# aiotdaan_r2.net
KiCad netlist of a schematic drawn in EAGLE
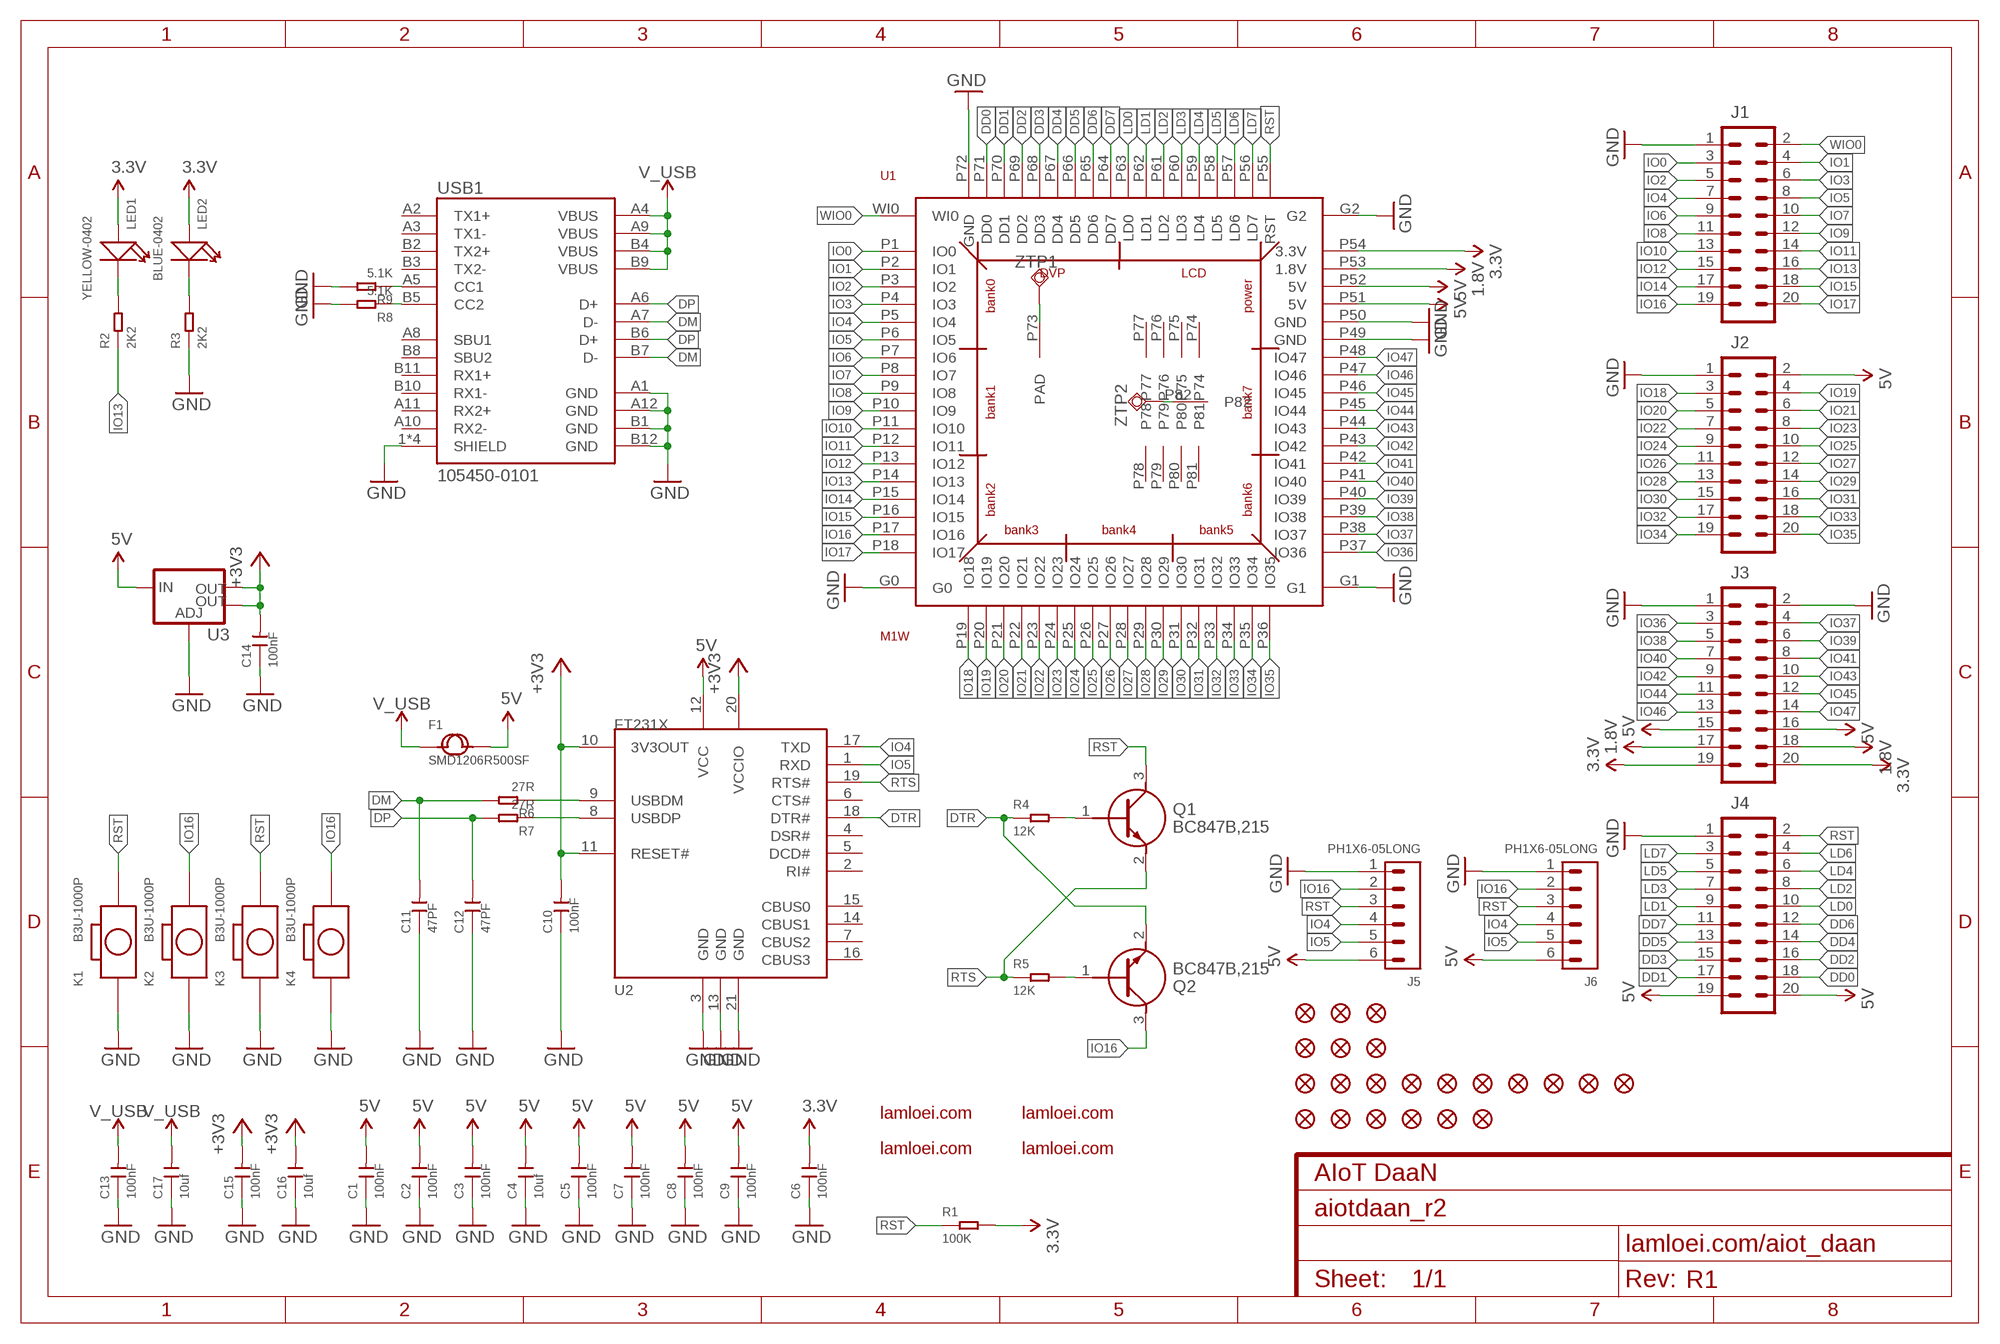
[diagram p0: schematic, sheet 1]

(export (version "E")
  (design (tool "Eeschema 10.0.6"))
  (components
    (comp (ref "C1")
      (value "100nF")
      (footprint "eagle-import:C0402")
      (fields (field (name "MPN") "CC0402JRNPO9BN470"))
      (libsource (lib "eagle-import") (part "CERAMIC-47PF-50V-5%-NP0(0402)"))
    )
    (comp (ref "C2")
      (value "100nF")
      (footprint "eagle-import:C0402")
      (fields (field (name "MPN") "CC0402JRNPO9BN470"))
      (libsource (lib "eagle-import") (part "CERAMIC-47PF-50V-5%-NP0(0402)"))
    )
    (comp (ref "C3")
      (value "100nF")
      (footprint "eagle-import:C0402")
      (fields (field (name "MPN") "CC0402JRNPO9BN470"))
      (libsource (lib "eagle-import") (part "CERAMIC-47PF-50V-5%-NP0(0402)"))
    )
    (comp (ref "C4")
      (value "10uf")
      (footprint "eagle-import:C0805")
      (fields (field (name "MPN") "CC0805MKX5R5BB226"))
      (libsource (lib "eagle-import") (part "CERAMIC-22UF-6.3V-20%-X5R(0805)"))
    )
    (comp (ref "C5")
      (value "100nF")
      (footprint "eagle-import:C0402")
      (fields (field (name "MPN") "CC0402JRNPO9BN470"))
      (libsource (lib "eagle-import") (part "CERAMIC-47PF-50V-5%-NP0(0402)"))
    )
    (comp (ref "C6")
      (value "100nF")
      (footprint "eagle-import:C0402")
      (fields (field (name "MPN") "CC0402JRNPO9BN470"))
      (libsource (lib "eagle-import") (part "CERAMIC-47PF-50V-5%-NP0(0402)"))
    )
    (comp (ref "C7")
      (value "100nF")
      (footprint "eagle-import:C0402")
      (fields (field (name "MPN") "CC0402JRNPO9BN470"))
      (libsource (lib "eagle-import") (part "CERAMIC-47PF-50V-5%-NP0(0402)"))
    )
    (comp (ref "C8")
      (value "100nF")
      (footprint "eagle-import:C0402")
      (fields (field (name "MPN") "CC0402JRNPO9BN470"))
      (libsource (lib "eagle-import") (part "CERAMIC-47PF-50V-5%-NP0(0402)"))
    )
    (comp (ref "C9")
      (value "100nF")
      (footprint "eagle-import:C0402")
      (fields (field (name "MPN") "CC0402JRNPO9BN470"))
      (libsource (lib "eagle-import") (part "CERAMIC-47PF-50V-5%-NP0(0402)"))
    )
    (comp (ref "C10")
      (value "100nF")
      (footprint "eagle-import:C0402")
      (fields (field (name "MPN") "CC0402JRNPO9BN470"))
      (libsource (lib "eagle-import") (part "CERAMIC-47PF-50V-5%-NP0(0402)"))
    )
    (comp (ref "C11")
      (value "47PF")
      (footprint "eagle-import:C0402")
      (fields (field (name "MPN") "CC0402JRNPO9BN470"))
      (libsource (lib "eagle-import") (part "CERAMIC-47PF-50V-5%-NP0(0402)"))
    )
    (comp (ref "C12")
      (value "47PF")
      (footprint "eagle-import:C0402")
      (fields (field (name "MPN") "CC0402JRNPO9BN470"))
      (libsource (lib "eagle-import") (part "CERAMIC-47PF-50V-5%-NP0(0402)"))
    )
    (comp (ref "C13")
      (value "100nF")
      (footprint "eagle-import:C0402")
      (fields (field (name "MPN") "CC0402JRNPO9BN470"))
      (libsource (lib "eagle-import") (part "CERAMIC-47PF-50V-5%-NP0(0402)"))
    )
    (comp (ref "C14")
      (value "100nF")
      (footprint "eagle-import:C0402")
      (fields (field (name "MPN") "CC0402JRNPO9BN470"))
      (libsource (lib "eagle-import") (part "CERAMIC-47PF-50V-5%-NP0(0402)"))
    )
    (comp (ref "C15")
      (value "100nF")
      (footprint "eagle-import:C0402")
      (fields (field (name "MPN") "CC0402JRNPO9BN470"))
      (libsource (lib "eagle-import") (part "CERAMIC-47PF-50V-5%-NP0(0402)"))
    )
    (comp (ref "C16")
      (value "10uf")
      (footprint "eagle-import:C0805")
      (fields (field (name "MPN") "CC0805MKX5R5BB226"))
      (libsource (lib "eagle-import") (part "CERAMIC-22UF-6.3V-20%-X5R(0805)"))
    )
    (comp (ref "C17")
      (value "10uf")
      (footprint "eagle-import:C0805")
      (fields (field (name "MPN") "CC0805MKX5R5BB226"))
      (libsource (lib "eagle-import") (part "CERAMIC-22UF-6.3V-20%-X5R(0805)"))
    )
    (comp (ref "F1")
      (value "SMD1206R500SF")
      (footprint "eagle-import:F1206")
      (libsource (lib "eagle-import") (part "SMD-PPTC-500MA(1206)"))
    )
    (comp (ref "J1")
      (value "M10X2")
      (footprint "eagle-import:2X10")
      (libsource (lib "eagle-import") (part "M10X2"))
    )
    (comp (ref "J2")
      (value "M10X2")
      (footprint "eagle-import:2X10")
      (libsource (lib "eagle-import") (part "M10X2"))
    )
    (comp (ref "J3")
      (value "M10X2")
      (footprint "eagle-import:2X10")
      (libsource (lib "eagle-import") (part "M10X2"))
    )
    (comp (ref "J4")
      (value "M10X2")
      (footprint "eagle-import:2X10")
      (libsource (lib "eagle-import") (part "M10X2"))
    )
    (comp (ref "J5")
      (value "PH1X6-05LONG")
      (footprint "eagle-import:PHL005-1-6")
      (libsource (lib "eagle-import") (part "PH1X6-05LONG"))
    )
    (comp (ref "J6")
      (value "PH1X6-05LONG")
      (footprint "eagle-import:PHL005-1-6")
      (libsource (lib "eagle-import") (part "PH1X6-05LONG"))
    )
    (comp (ref "K1")
      (value "B3U-1000P")
      (footprint "eagle-import:SW2-SMD-3.0X2.5X1.2+0.4MM")
      (libsource (lib "eagle-import") (part "SMD-BUTTON-WITHOUT-BOSS-(2P-3X2.5MM)"))
    )
    (comp (ref "K2")
      (value "B3U-1000P")
      (footprint "eagle-import:SW2-SMD-3.0X2.5X1.2+0.4MM")
      (libsource (lib "eagle-import") (part "SMD-BUTTON-WITHOUT-BOSS-(2P-3X2.5MM)"))
    )
    (comp (ref "K3")
      (value "B3U-1000P")
      (footprint "eagle-import:SW2-SMD-3.0X2.5X1.2+0.4MM")
      (libsource (lib "eagle-import") (part "SMD-BUTTON-WITHOUT-BOSS-(2P-3X2.5MM)"))
    )
    (comp (ref "K4")
      (value "B3U-1000P")
      (footprint "eagle-import:SW2-SMD-3.0X2.5X1.2+0.4MM")
      (libsource (lib "eagle-import") (part "SMD-BUTTON-WITHOUT-BOSS-(2P-3X2.5MM)"))
    )
    (comp (ref "LED1")
      (value "YELLOW-0402")
      (footprint "eagle-import:LED-0402")
      (fields (field (name "MPN") "BL-HB337A-AV-TRB"))
      (libsource (lib "eagle-import") (part "SMD-LED-CLEAR-BLUE(0402)"))
    )
    (comp (ref "LED2")
      (value "BLUE-0402")
      (footprint "eagle-import:LED-0402")
      (fields (field (name "MPN") "BL-HB337A-AV-TRB"))
      (libsource (lib "eagle-import") (part "SMD-LED-CLEAR-BLUE(0402)"))
    )
    (comp (ref "Q1")
      (value "BC847B,215")
      (footprint "eagle-import:SOT95P230X110-3N")
      (fields (field (name "RS_PART_NUMBER") "4367947P"))
      (libsource (lib "eagle-import") (part "BC847B,215"))
    )
    (comp (ref "Q2")
      (value "BC847B,215")
      (footprint "eagle-import:SOT95P230X110-3N")
      (fields (field (name "RS_PART_NUMBER") "4367947P"))
      (libsource (lib "eagle-import") (part "BC847B,215"))
    )
    (comp (ref "R1")
      (value "100K")
      (footprint "eagle-import:R0402")
      (fields (field (name "MPN") "RC0402FR-0722RL"))
      (libsource (lib "eagle-import") (part "SMD-RES-22R-1%-1/16W(0402)"))
    )
    (comp (ref "R2")
      (value "2K2")
      (footprint "eagle-import:R0402")
      (fields (field (name "MPN") "RC0402FR-0722RL"))
      (libsource (lib "eagle-import") (part "SMD-RES-22R-1%-1/16W(0402)"))
    )
    (comp (ref "R3")
      (value "2K2")
      (footprint "eagle-import:R0402")
      (fields (field (name "MPN") "RC0402FR-0722RL"))
      (libsource (lib "eagle-import") (part "SMD-RES-22R-1%-1/16W(0402)"))
    )
    (comp (ref "R4")
      (value "12K")
      (footprint "eagle-import:R0402")
      (fields (field (name "MPN") "RC0402FR-0722RL"))
      (libsource (lib "eagle-import") (part "SMD-RES-22R-1%-1/16W(0402)"))
    )
    (comp (ref "R5")
      (value "12K")
      (footprint "eagle-import:R0402")
      (fields (field (name "MPN") "RC0402FR-0722RL"))
      (libsource (lib "eagle-import") (part "SMD-RES-22R-1%-1/16W(0402)"))
    )
    (comp (ref "R6")
      (value "27R")
      (footprint "eagle-import:R0402")
      (fields (field (name "MPN") "RC0402FR-0722RL"))
      (libsource (lib "eagle-import") (part "SMD-RES-22R-1%-1/16W(0402)"))
    )
    (comp (ref "R7")
      (value "27R")
      (footprint "eagle-import:R0402")
      (fields (field (name "MPN") "RC0402FR-0722RL"))
      (libsource (lib "eagle-import") (part "SMD-RES-22R-1%-1/16W(0402)"))
    )
    (comp (ref "R8")
      (value "5.1K")
      (footprint "eagle-import:R0402")
      (fields (field (name "MPN") "RC0402FR-0722RL"))
      (libsource (lib "eagle-import") (part "SMD-RES-22R-1%-1/16W(0402)"))
    )
    (comp (ref "R9")
      (value "5.1K")
      (footprint "eagle-import:R0402")
      (fields (field (name "MPN") "RC0402FR-0722RL"))
      (libsource (lib "eagle-import") (part "SMD-RES-22R-1%-1/16W(0402)"))
    )
    (comp (ref "U1")
      (value "M1W")
      (footprint "eagle-import:M1W")
      (libsource (lib "eagle-import") (part "M1W"))
    )
    (comp (ref "U2")
      (value "FT231X-Q")
      (footprint "eagle-import:QFN20")
      (libsource (lib "eagle-import") (part "FT231X-Q"))
    )
    (comp (ref "U3")
      (value "V_REG_LM1117SOT223")
      (footprint "eagle-import:SOT223")
      (libsource (lib "eagle-import") (part "V_REG_LM1117SOT223"))
    )
    (comp (ref "USB1")
      (value "105450-0101")
      (footprint "eagle-import:MOLEX_105450-0101")
      (fields (field (name "MF") "Molex"))
      (libsource (lib "eagle-import") (part "105450-0101"))
    )
    (comp (ref "ZFCB1")
      (value "FIDUCIAL1X2")
      (footprint "eagle-import:FIDUCIAL-1X2")
      (libsource (lib "eagle-import") (part "FIDUCIAL1X2"))
    )
    (comp (ref "ZFCB2")
      (value "FIDUCIAL1X2")
      (footprint "eagle-import:FIDUCIAL-1X2")
      (libsource (lib "eagle-import") (part "FIDUCIAL1X2"))
    )
    (comp (ref "ZFCB3")
      (value "FIDUCIAL1X2")
      (footprint "eagle-import:FIDUCIAL-1X2")
      (libsource (lib "eagle-import") (part "FIDUCIAL1X2"))
    )
    (comp (ref "ZFCT1")
      (value "FIDUCIAL1X2")
      (footprint "eagle-import:FIDUCIAL-1X2")
      (libsource (lib "eagle-import") (part "FIDUCIAL1X2"))
    )
    (comp (ref "ZFCT2")
      (value "FIDUCIAL1X2")
      (footprint "eagle-import:FIDUCIAL-1X2")
      (libsource (lib "eagle-import") (part "FIDUCIAL1X2"))
    )
    (comp (ref "ZFCT3")
      (value "FIDUCIAL1X2")
      (footprint "eagle-import:FIDUCIAL-1X2")
      (libsource (lib "eagle-import") (part "FIDUCIAL1X2"))
    )
    (comp (ref "ZFDB1")
      (value "FIDUCIAL1X2")
      (footprint "eagle-import:FIDUCIAL-1X2")
      (libsource (lib "eagle-import") (part "FIDUCIAL1X2"))
    )
    (comp (ref "ZFDB2")
      (value "FIDUCIAL1X2")
      (footprint "eagle-import:FIDUCIAL-1X2")
      (libsource (lib "eagle-import") (part "FIDUCIAL1X2"))
    )
    (comp (ref "ZFDB3")
      (value "FIDUCIAL1X2")
      (footprint "eagle-import:FIDUCIAL-1X2")
      (libsource (lib "eagle-import") (part "FIDUCIAL1X2"))
    )
    (comp (ref "ZFDB4")
      (value "FIDUCIAL1X2")
      (footprint "eagle-import:FIDUCIAL-1X2")
      (libsource (lib "eagle-import") (part "FIDUCIAL1X2"))
    )
    (comp (ref "ZFDB5")
      (value "FIDUCIAL1X2")
      (footprint "eagle-import:FIDUCIAL-1X2")
      (libsource (lib "eagle-import") (part "FIDUCIAL1X2"))
    )
    (comp (ref "ZFDB6")
      (value "FIDUCIAL1X2")
      (footprint "eagle-import:FIDUCIAL-1X2")
      (libsource (lib "eagle-import") (part "FIDUCIAL1X2"))
    )
    (comp (ref "ZFDT1")
      (value "FIDUCIAL1X2")
      (footprint "eagle-import:FIDUCIAL-1X2")
      (libsource (lib "eagle-import") (part "FIDUCIAL1X2"))
    )
    (comp (ref "ZFDT2")
      (value "FIDUCIAL1X2")
      (footprint "eagle-import:FIDUCIAL-1X2")
      (libsource (lib "eagle-import") (part "FIDUCIAL1X2"))
    )
    (comp (ref "ZFDT3")
      (value "FIDUCIAL1X2")
      (footprint "eagle-import:FIDUCIAL-1X2")
      (libsource (lib "eagle-import") (part "FIDUCIAL1X2"))
    )
    (comp (ref "ZFDT4")
      (value "FIDUCIAL1X2")
      (footprint "eagle-import:FIDUCIAL-1X2")
      (libsource (lib "eagle-import") (part "FIDUCIAL1X2"))
    )
    (comp (ref "ZFDT5")
      (value "FIDUCIAL1X2")
      (footprint "eagle-import:FIDUCIAL-1X2")
      (libsource (lib "eagle-import") (part "FIDUCIAL1X2"))
    )
    (comp (ref "ZFDT6")
      (value "FIDUCIAL1X2")
      (footprint "eagle-import:FIDUCIAL-1X2")
      (libsource (lib "eagle-import") (part "FIDUCIAL1X2"))
    )
    (comp (ref "ZFDT7")
      (value "FIDUCIAL1X2")
      (footprint "eagle-import:FIDUCIAL-1X2")
      (libsource (lib "eagle-import") (part "FIDUCIAL1X2"))
    )
    (comp (ref "ZFDT8")
      (value "FIDUCIAL1X2")
      (footprint "eagle-import:FIDUCIAL-1X2")
      (libsource (lib "eagle-import") (part "FIDUCIAL1X2"))
    )
    (comp (ref "ZFDT9")
      (value "FIDUCIAL1X2")
      (footprint "eagle-import:FIDUCIAL-1X2")
      (libsource (lib "eagle-import") (part "FIDUCIAL1X2"))
    )
    (comp (ref "ZFDT10")
      (value "FIDUCIAL1X2")
      (footprint "eagle-import:FIDUCIAL-1X2")
      (libsource (lib "eagle-import") (part "FIDUCIAL1X2"))
    )
    (comp (ref "ZL1")
      (value "LAMLOEI_BIGLOGO")
      (footprint "eagle-import:LAMLOEI_BIGLOGO")
      (libsource (lib "eagle-import") (part "LAMLOEI_BIGLOGO"))
    )
    (comp (ref "ZL2")
      (value "LAMLOEI_BIGLOGO")
      (footprint "eagle-import:LAMLOEI_BIGLOGO")
      (libsource (lib "eagle-import") (part "LAMLOEI_BIGLOGO"))
    )
    (comp (ref "ZL3")
      (value "LAMLEOI_LOGO_3")
      (footprint "eagle-import:LAMLEOI_LOGO_3")
      (libsource (lib "eagle-import") (part "LAMLEOI_LOGO_3"))
    )
    (comp (ref "ZL4")
      (value "LAMLEOI_LOGO_3")
      (footprint "eagle-import:LAMLEOI_LOGO_3")
      (libsource (lib "eagle-import") (part "LAMLEOI_LOGO_3"))
    )
    (comp (ref "ZTP1")
      (value "TPSQTP20SQ")
      (footprint "eagle-import:TP20SQ")
      (libsource (lib "eagle-import") (part "TPSQTP20SQ"))
    )
    (comp (ref "ZTP2")
      (value "TPSQTP20SQ")
      (footprint "eagle-import:TP20SQ")
      (libsource (lib "eagle-import") (part "TPSQTP20SQ"))
    )
  )
  (nets
    (net (code "1") (name "+3V3") (class "Default")
      (node (ref "C10") (pin "2") (pinfunction "2_2") (pintype "passive"))
      (node (ref "C14") (pin "2") (pinfunction "2_2") (pintype "passive"))
      (node (ref "C15") (pin "2") (pinfunction "2_2") (pintype "passive"))
      (node (ref "C16") (pin "2") (pinfunction "2_2") (pintype "passive"))
      (node (ref "U2") (pin "10") (pinfunction "3V3OUT_10") (pintype "bidirectional"))
      (node (ref "U2") (pin "11") (pinfunction "RESET#_11") (pintype "bidirectional"))
      (node (ref "U2") (pin "20") (pinfunction "VCCIO_20") (pintype "bidirectional"))
      (node (ref "U3") (pin "2") (pinfunction "OUT_2") (pintype "output"))
      (node (ref "U3") (pin "4") (pinfunction "OUT_4") (pintype "output"))
    )
    (net (code "2") (name "1.8V") (class "Default")
      (node (ref "J3") (pin "17") (pinfunction "17_17") (pintype "passive"))
      (node (ref "J3") (pin "18") (pinfunction "18_18") (pintype "passive"))
      (node (ref "U1") (pin "P53") (pinfunction "1.8V_P53") (pintype "power_in"))
    )
    (net (code "3") (name "3.3V") (class "Default")
      (node (ref "C6") (pin "2") (pinfunction "2_2") (pintype "passive"))
      (node (ref "J3") (pin "19") (pinfunction "19_19") (pintype "passive"))
      (node (ref "J3") (pin "20") (pinfunction "20_20") (pintype "passive"))
      (node (ref "LED1") (pin "+") (pinfunction "+_+") (pintype "passive"))
      (node (ref "LED2") (pin "+") (pinfunction "+_+") (pintype "passive"))
      (node (ref "R1") (pin "2") (pinfunction "2_2") (pintype "passive"))
      (node (ref "U1") (pin "P54") (pinfunction "3.3V_P54") (pintype "power_in"))
    )
    (net (code "4") (name "5V") (class "Default")
      (node (ref "C1") (pin "2") (pinfunction "2_2") (pintype "passive"))
      (node (ref "C2") (pin "2") (pinfunction "2_2") (pintype "passive"))
      (node (ref "C3") (pin "2") (pinfunction "2_2") (pintype "passive"))
      (node (ref "C4") (pin "2") (pinfunction "2_2") (pintype "passive"))
      (node (ref "C5") (pin "2") (pinfunction "2_2") (pintype "passive"))
      (node (ref "C7") (pin "2") (pinfunction "2_2") (pintype "passive"))
      (node (ref "C8") (pin "2") (pinfunction "2_2") (pintype "passive"))
      (node (ref "C9") (pin "2") (pinfunction "2_2") (pintype "passive"))
      (node (ref "F1") (pin "2") (pinfunction "2_2") (pintype "bidirectional"))
      (node (ref "J2") (pin "2") (pinfunction "2_2") (pintype "passive"))
      (node (ref "J3") (pin "15") (pinfunction "15_15") (pintype "passive"))
      (node (ref "J3") (pin "16") (pinfunction "16_16") (pintype "passive"))
      (node (ref "J4") (pin "19") (pinfunction "19_19") (pintype "passive"))
      (node (ref "J4") (pin "20") (pinfunction "20_20") (pintype "passive"))
      (node (ref "J5") (pin "6") (pinfunction "6_6") (pintype "bidirectional"))
      (node (ref "J6") (pin "6") (pinfunction "6_6") (pintype "bidirectional"))
      (node (ref "U1") (pin "P51") (pinfunction "5V_P51") (pintype "power_in"))
      (node (ref "U1") (pin "P52") (pinfunction "5V_P52") (pintype "power_in"))
      (node (ref "U2") (pin "12") (pinfunction "VCC_12") (pintype "bidirectional"))
      (node (ref "U3") (pin "3") (pinfunction "IN_3") (pintype "input"))
    )
    (net (code "5") (name "DD0") (class "Default")
      (node (ref "J4") (pin "18") (pinfunction "18_18") (pintype "passive"))
      (node (ref "U1") (pin "P71") (pinfunction "DD0_P71") (pintype "bidirectional"))
    )
    (net (code "6") (name "DD1") (class "Default")
      (node (ref "J4") (pin "17") (pinfunction "17_17") (pintype "passive"))
      (node (ref "U1") (pin "P70") (pinfunction "DD1_P70") (pintype "bidirectional"))
    )
    (net (code "7") (name "DD2") (class "Default")
      (node (ref "J4") (pin "16") (pinfunction "16_16") (pintype "passive"))
      (node (ref "U1") (pin "P69") (pinfunction "DD2_P69") (pintype "bidirectional"))
    )
    (net (code "8") (name "DD3") (class "Default")
      (node (ref "J4") (pin "15") (pinfunction "15_15") (pintype "passive"))
      (node (ref "U1") (pin "P68") (pinfunction "DD3_P68") (pintype "bidirectional"))
    )
    (net (code "9") (name "DD4") (class "Default")
      (node (ref "J4") (pin "14") (pinfunction "14_14") (pintype "passive"))
      (node (ref "U1") (pin "P67") (pinfunction "DD4_P67") (pintype "bidirectional"))
    )
    (net (code "10") (name "DD5") (class "Default")
      (node (ref "J4") (pin "13") (pinfunction "13_13") (pintype "passive"))
      (node (ref "U1") (pin "P66") (pinfunction "DD5_P66") (pintype "bidirectional"))
    )
    (net (code "11") (name "DD6") (class "Default")
      (node (ref "J4") (pin "12") (pinfunction "12_12") (pintype "passive"))
      (node (ref "U1") (pin "P65") (pinfunction "DD6_P65") (pintype "bidirectional"))
    )
    (net (code "12") (name "DD7") (class "Default")
      (node (ref "J4") (pin "11") (pinfunction "11_11") (pintype "passive"))
      (node (ref "U1") (pin "P64") (pinfunction "DD7_P64") (pintype "bidirectional"))
    )
    (net (code "13") (name "DM") (class "Default")
      (node (ref "C11") (pin "2") (pinfunction "2_2") (pintype "passive"))
      (node (ref "R6") (pin "2") (pinfunction "2_2") (pintype "passive"))
      (node (ref "USB1") (pin "A7") (pinfunction "D-_A7") (pintype "bidirectional"))
      (node (ref "USB1") (pin "B7") (pinfunction "D-_B7") (pintype "bidirectional"))
    )
    (net (code "14") (name "DP") (class "Default")
      (node (ref "C12") (pin "2") (pinfunction "2_2") (pintype "passive"))
      (node (ref "R7") (pin "2") (pinfunction "2_2") (pintype "passive"))
      (node (ref "USB1") (pin "A6") (pinfunction "D+_A6") (pintype "bidirectional"))
      (node (ref "USB1") (pin "B6") (pinfunction "D+_B6") (pintype "bidirectional"))
    )
    (net (code "15") (name "DTR") (class "Default")
      (node (ref "Q2") (pin "2") (pinfunction "E_2") (pintype "bidirectional"))
      (node (ref "R4") (pin "1") (pinfunction "1_1") (pintype "passive"))
      (node (ref "U2") (pin "18") (pinfunction "DTR#_18") (pintype "bidirectional"))
    )
    (net (code "16") (name "GND") (class "Default")
      (node (ref "C1") (pin "1") (pinfunction "1_1") (pintype "passive"))
      (node (ref "C10") (pin "1") (pinfunction "1_1") (pintype "passive"))
      (node (ref "C11") (pin "1") (pinfunction "1_1") (pintype "passive"))
      (node (ref "C12") (pin "1") (pinfunction "1_1") (pintype "passive"))
      (node (ref "C13") (pin "1") (pinfunction "1_1") (pintype "passive"))
      (node (ref "C14") (pin "1") (pinfunction "1_1") (pintype "passive"))
      (node (ref "C15") (pin "1") (pinfunction "1_1") (pintype "passive"))
      (node (ref "C16") (pin "1") (pinfunction "1_1") (pintype "passive"))
      (node (ref "C17") (pin "1") (pinfunction "1_1") (pintype "passive"))
      (node (ref "C2") (pin "1") (pinfunction "1_1") (pintype "passive"))
      (node (ref "C3") (pin "1") (pinfunction "1_1") (pintype "passive"))
      (node (ref "C4") (pin "1") (pinfunction "1_1") (pintype "passive"))
      (node (ref "C5") (pin "1") (pinfunction "1_1") (pintype "passive"))
      (node (ref "C6") (pin "1") (pinfunction "1_1") (pintype "passive"))
      (node (ref "C7") (pin "1") (pinfunction "1_1") (pintype "passive"))
      (node (ref "C8") (pin "1") (pinfunction "1_1") (pintype "passive"))
      (node (ref "C9") (pin "1") (pinfunction "1_1") (pintype "passive"))
      (node (ref "J1") (pin "1") (pinfunction "1_1") (pintype "passive"))
      (node (ref "J2") (pin "1") (pinfunction "1_1") (pintype "passive"))
      (node (ref "J3") (pin "1") (pinfunction "1_1") (pintype "passive"))
      (node (ref "J3") (pin "2") (pinfunction "2_2") (pintype "passive"))
      (node (ref "J4") (pin "1") (pinfunction "1_1") (pintype "passive"))
      (node (ref "J5") (pin "1") (pinfunction "1_1") (pintype "bidirectional"))
      (node (ref "J6") (pin "1") (pinfunction "1_1") (pintype "bidirectional"))
      (node (ref "K1") (pin "1") (pinfunction "1_1") (pintype "bidirectional"))
      (node (ref "K2") (pin "1") (pinfunction "1_1") (pintype "bidirectional"))
      (node (ref "K3") (pin "1") (pinfunction "1_1") (pintype "bidirectional"))
      (node (ref "K4") (pin "1") (pinfunction "1_1") (pintype "bidirectional"))
      (node (ref "R3") (pin "1") (pinfunction "1_1") (pintype "passive"))
      (node (ref "R8") (pin "2") (pinfunction "2_2") (pintype "passive"))
      (node (ref "R9") (pin "2") (pinfunction "2_2") (pintype "passive"))
      (node (ref "U1") (pin "G0") (pinfunction "G0_G0") (pintype "power_in"))
      (node (ref "U1") (pin "G1") (pinfunction "G1_G1") (pintype "power_in"))
      (node (ref "U1") (pin "G2") (pinfunction "G2_G2") (pintype "power_in"))
      (node (ref "U1") (pin "P49") (pinfunction "GND_P49") (pintype "power_in"))
      (node (ref "U1") (pin "P50") (pinfunction "GND_P50") (pintype "power_in"))
      (node (ref "U1") (pin "P72") (pinfunction "GND_P72") (pintype "power_in"))
      (node (ref "U2") (pin "13") (pinfunction "GND_13") (pintype "bidirectional"))
      (node (ref "U2") (pin "21") (pinfunction "GND_21") (pintype "bidirectional"))
      (node (ref "U2") (pin "3") (pinfunction "GND_3") (pintype "bidirectional"))
      (node (ref "U3") (pin "1") (pinfunction "ADJ_1") (pintype "input"))
      (node (ref "USB1") (pin "1") (pinfunction "SHIELD_1") (pintype "power_in"))
      (node (ref "USB1") (pin "2") (pinfunction "SHIELD_2") (pintype "power_in"))
      (node (ref "USB1") (pin "3") (pinfunction "SHIELD_3") (pintype "power_in"))
      (node (ref "USB1") (pin "4") (pinfunction "SHIELD_4") (pintype "power_in"))
      (node (ref "USB1") (pin "A1") (pinfunction "GND_A1") (pintype "power_in"))
      (node (ref "USB1") (pin "A12") (pinfunction "GND_A12") (pintype "power_in"))
      (node (ref "USB1") (pin "B1") (pinfunction "GND_B1") (pintype "power_in"))
      (node (ref "USB1") (pin "B12") (pinfunction "GND_B12") (pintype "power_in"))
    )
    (net (code "17") (name "IO0") (class "Default")
      (node (ref "J1") (pin "3") (pinfunction "3_3") (pintype "passive"))
      (node (ref "U1") (pin "P1") (pinfunction "IO0_P1") (pintype "bidirectional"))
    )
    (net (code "18") (name "IO1") (class "Default")
      (node (ref "J1") (pin "4") (pinfunction "4_4") (pintype "passive"))
      (node (ref "U1") (pin "P2") (pinfunction "IO1_P2") (pintype "bidirectional"))
    )
    (net (code "19") (name "IO2") (class "Default")
      (node (ref "J1") (pin "5") (pinfunction "5_5") (pintype "passive"))
      (node (ref "U1") (pin "P3") (pinfunction "IO2_P3") (pintype "bidirectional"))
    )
    (net (code "20") (name "IO3") (class "Default")
      (node (ref "J1") (pin "6") (pinfunction "6_6") (pintype "passive"))
      (node (ref "U1") (pin "P4") (pinfunction "IO3_P4") (pintype "bidirectional"))
    )
    (net (code "21") (name "IO4") (class "Default")
      (node (ref "J1") (pin "7") (pinfunction "7_7") (pintype "passive"))
      (node (ref "J5") (pin "4") (pinfunction "4_4") (pintype "bidirectional"))
      (node (ref "J6") (pin "4") (pinfunction "4_4") (pintype "bidirectional"))
      (node (ref "U1") (pin "P5") (pinfunction "IO4_P5") (pintype "bidirectional"))
      (node (ref "U2") (pin "17") (pinfunction "TXD_17") (pintype "bidirectional"))
    )
    (net (code "22") (name "IO5") (class "Default")
      (node (ref "J1") (pin "8") (pinfunction "8_8") (pintype "passive"))
      (node (ref "J5") (pin "5") (pinfunction "5_5") (pintype "bidirectional"))
      (node (ref "J6") (pin "5") (pinfunction "5_5") (pintype "bidirectional"))
      (node (ref "U1") (pin "P6") (pinfunction "IO5_P6") (pintype "bidirectional"))
      (node (ref "U2") (pin "1") (pinfunction "RXD_1") (pintype "bidirectional"))
    )
    (net (code "23") (name "IO6") (class "Default")
      (node (ref "J1") (pin "9") (pinfunction "9_9") (pintype "passive"))
      (node (ref "U1") (pin "P7") (pinfunction "IO6_P7") (pintype "bidirectional"))
    )
    (net (code "24") (name "IO7") (class "Default")
      (node (ref "J1") (pin "10") (pinfunction "10_10") (pintype "passive"))
      (node (ref "U1") (pin "P8") (pinfunction "IO7_P8") (pintype "bidirectional"))
    )
    (net (code "25") (name "IO8") (class "Default")
      (node (ref "J1") (pin "11") (pinfunction "11_11") (pintype "passive"))
      (node (ref "U1") (pin "P9") (pinfunction "IO8_P9") (pintype "bidirectional"))
    )
    (net (code "26") (name "IO9") (class "Default")
      (node (ref "J1") (pin "12") (pinfunction "12_12") (pintype "passive"))
      (node (ref "U1") (pin "P10") (pinfunction "IO9_P10") (pintype "bidirectional"))
    )
    (net (code "27") (name "IO10") (class "Default")
      (node (ref "J1") (pin "13") (pinfunction "13_13") (pintype "passive"))
      (node (ref "U1") (pin "P11") (pinfunction "IO10_P11") (pintype "bidirectional"))
    )
    (net (code "28") (name "IO11") (class "Default")
      (node (ref "J1") (pin "14") (pinfunction "14_14") (pintype "passive"))
      (node (ref "U1") (pin "P12") (pinfunction "IO11_P12") (pintype "bidirectional"))
    )
    (net (code "29") (name "IO12") (class "Default")
      (node (ref "J1") (pin "15") (pinfunction "15_15") (pintype "passive"))
      (node (ref "U1") (pin "P13") (pinfunction "IO12_P13") (pintype "bidirectional"))
    )
    (net (code "30") (name "IO13") (class "Default")
      (node (ref "J1") (pin "16") (pinfunction "16_16") (pintype "passive"))
      (node (ref "R2") (pin "1") (pinfunction "1_1") (pintype "passive"))
      (node (ref "U1") (pin "P14") (pinfunction "IO13_P14") (pintype "bidirectional"))
    )
    (net (code "31") (name "IO14") (class "Default")
      (node (ref "J1") (pin "17") (pinfunction "17_17") (pintype "passive"))
      (node (ref "U1") (pin "P15") (pinfunction "IO14_P15") (pintype "bidirectional"))
    )
    (net (code "32") (name "IO15") (class "Default")
      (node (ref "J1") (pin "18") (pinfunction "18_18") (pintype "passive"))
      (node (ref "U1") (pin "P16") (pinfunction "IO15_P16") (pintype "bidirectional"))
    )
    (net (code "33") (name "IO16") (class "Default")
      (node (ref "J1") (pin "19") (pinfunction "19_19") (pintype "passive"))
      (node (ref "J5") (pin "2") (pinfunction "2_2") (pintype "bidirectional"))
      (node (ref "J6") (pin "2") (pinfunction "2_2") (pintype "bidirectional"))
      (node (ref "K2") (pin "2") (pinfunction "2_2") (pintype "bidirectional"))
      (node (ref "K4") (pin "2") (pinfunction "2_2") (pintype "bidirectional"))
      (node (ref "Q2") (pin "3") (pinfunction "C_3") (pintype "bidirectional"))
      (node (ref "U1") (pin "P17") (pinfunction "IO16_P17") (pintype "bidirectional"))
    )
    (net (code "34") (name "IO17") (class "Default")
      (node (ref "J1") (pin "20") (pinfunction "20_20") (pintype "passive"))
      (node (ref "U1") (pin "P18") (pinfunction "IO17_P18") (pintype "bidirectional"))
    )
    (net (code "35") (name "IO18") (class "Default")
      (node (ref "J2") (pin "3") (pinfunction "3_3") (pintype "passive"))
      (node (ref "U1") (pin "P19") (pinfunction "IO18_P19") (pintype "bidirectional"))
    )
    (net (code "36") (name "IO19") (class "Default")
      (node (ref "J2") (pin "4") (pinfunction "4_4") (pintype "passive"))
      (node (ref "U1") (pin "P20") (pinfunction "IO19_P20") (pintype "bidirectional"))
    )
    (net (code "37") (name "IO20") (class "Default")
      (node (ref "J2") (pin "5") (pinfunction "5_5") (pintype "passive"))
      (node (ref "U1") (pin "P21") (pinfunction "IO20_P21") (pintype "bidirectional"))
    )
    (net (code "38") (name "IO21") (class "Default")
      (node (ref "J2") (pin "6") (pinfunction "6_6") (pintype "passive"))
      (node (ref "U1") (pin "P22") (pinfunction "IO21_P22") (pintype "bidirectional"))
    )
    (net (code "39") (name "IO22") (class "Default")
      (node (ref "J2") (pin "7") (pinfunction "7_7") (pintype "passive"))
      (node (ref "U1") (pin "P23") (pinfunction "IO22_P23") (pintype "bidirectional"))
    )
    (net (code "40") (name "IO23") (class "Default")
      (node (ref "J2") (pin "8") (pinfunction "8_8") (pintype "passive"))
      (node (ref "U1") (pin "P24") (pinfunction "IO23_P24") (pintype "bidirectional"))
    )
    (net (code "41") (name "IO24") (class "Default")
      (node (ref "J2") (pin "9") (pinfunction "9_9") (pintype "passive"))
      (node (ref "U1") (pin "P25") (pinfunction "IO24_P25") (pintype "bidirectional"))
    )
    (net (code "42") (name "IO25") (class "Default")
      (node (ref "J2") (pin "10") (pinfunction "10_10") (pintype "passive"))
      (node (ref "U1") (pin "P26") (pinfunction "IO25_P26") (pintype "bidirectional"))
    )
    (net (code "43") (name "IO26") (class "Default")
      (node (ref "J2") (pin "11") (pinfunction "11_11") (pintype "passive"))
      (node (ref "U1") (pin "P27") (pinfunction "IO26_P27") (pintype "bidirectional"))
    )
    (net (code "44") (name "IO27") (class "Default")
      (node (ref "J2") (pin "12") (pinfunction "12_12") (pintype "passive"))
      (node (ref "U1") (pin "P28") (pinfunction "IO27_P28") (pintype "bidirectional"))
    )
    (net (code "45") (name "IO28") (class "Default")
      (node (ref "J2") (pin "13") (pinfunction "13_13") (pintype "passive"))
      (node (ref "U1") (pin "P29") (pinfunction "IO28_P29") (pintype "bidirectional"))
    )
    (net (code "46") (name "IO29") (class "Default")
      (node (ref "J2") (pin "14") (pinfunction "14_14") (pintype "passive"))
      (node (ref "U1") (pin "P30") (pinfunction "IO29_P30") (pintype "bidirectional"))
    )
    (net (code "47") (name "IO30") (class "Default")
      (node (ref "J2") (pin "15") (pinfunction "15_15") (pintype "passive"))
      (node (ref "U1") (pin "P31") (pinfunction "IO30_P31") (pintype "bidirectional"))
    )
    (net (code "48") (name "IO31") (class "Default")
      (node (ref "J2") (pin "16") (pinfunction "16_16") (pintype "passive"))
      (node (ref "U1") (pin "P32") (pinfunction "IO31_P32") (pintype "bidirectional"))
    )
    (net (code "49") (name "IO32") (class "Default")
      (node (ref "J2") (pin "17") (pinfunction "17_17") (pintype "passive"))
      (node (ref "U1") (pin "P33") (pinfunction "IO32_P33") (pintype "bidirectional"))
    )
    (net (code "50") (name "IO33") (class "Default")
      (node (ref "J2") (pin "18") (pinfunction "18_18") (pintype "passive"))
      (node (ref "U1") (pin "P34") (pinfunction "IO33_P34") (pintype "bidirectional"))
    )
    (net (code "51") (name "IO34") (class "Default")
      (node (ref "J2") (pin "19") (pinfunction "19_19") (pintype "passive"))
      (node (ref "U1") (pin "P35") (pinfunction "IO34_P35") (pintype "bidirectional"))
    )
    (net (code "52") (name "IO35") (class "Default")
      (node (ref "J2") (pin "20") (pinfunction "20_20") (pintype "passive"))
      (node (ref "U1") (pin "P36") (pinfunction "IO35_P36") (pintype "bidirectional"))
    )
    (net (code "53") (name "IO36") (class "Default")
      (node (ref "J3") (pin "3") (pinfunction "3_3") (pintype "passive"))
      (node (ref "U1") (pin "P37") (pinfunction "IO36_P37") (pintype "bidirectional"))
    )
    (net (code "54") (name "IO37") (class "Default")
      (node (ref "J3") (pin "4") (pinfunction "4_4") (pintype "passive"))
      (node (ref "U1") (pin "P38") (pinfunction "IO37_P38") (pintype "bidirectional"))
    )
    (net (code "55") (name "IO38") (class "Default")
      (node (ref "J3") (pin "5") (pinfunction "5_5") (pintype "passive"))
      (node (ref "U1") (pin "P39") (pinfunction "IO38_P39") (pintype "bidirectional"))
    )
    (net (code "56") (name "IO39") (class "Default")
      (node (ref "J3") (pin "6") (pinfunction "6_6") (pintype "passive"))
      (node (ref "U1") (pin "P40") (pinfunction "IO39_P40") (pintype "bidirectional"))
    )
    (net (code "57") (name "IO40") (class "Default")
      (node (ref "J3") (pin "7") (pinfunction "7_7") (pintype "passive"))
      (node (ref "U1") (pin "P41") (pinfunction "IO40_P41") (pintype "bidirectional"))
    )
    (net (code "58") (name "IO41") (class "Default")
      (node (ref "J3") (pin "8") (pinfunction "8_8") (pintype "passive"))
      (node (ref "U1") (pin "P42") (pinfunction "IO41_P42") (pintype "bidirectional"))
    )
    (net (code "59") (name "IO42") (class "Default")
      (node (ref "J3") (pin "9") (pinfunction "9_9") (pintype "passive"))
      (node (ref "U1") (pin "P43") (pinfunction "IO42_P43") (pintype "bidirectional"))
    )
    (net (code "60") (name "IO43") (class "Default")
      (node (ref "J3") (pin "10") (pinfunction "10_10") (pintype "passive"))
      (node (ref "U1") (pin "P44") (pinfunction "IO43_P44") (pintype "bidirectional"))
    )
    (net (code "61") (name "IO44") (class "Default")
      (node (ref "J3") (pin "11") (pinfunction "11_11") (pintype "passive"))
      (node (ref "U1") (pin "P45") (pinfunction "IO44_P45") (pintype "bidirectional"))
    )
    (net (code "62") (name "IO45") (class "Default")
      (node (ref "J3") (pin "12") (pinfunction "12_12") (pintype "passive"))
      (node (ref "U1") (pin "P46") (pinfunction "IO45_P46") (pintype "bidirectional"))
    )
    (net (code "63") (name "IO46") (class "Default")
      (node (ref "J3") (pin "13") (pinfunction "13_13") (pintype "passive"))
      (node (ref "U1") (pin "P47") (pinfunction "IO46_P47") (pintype "bidirectional"))
    )
    (net (code "64") (name "IO47") (class "Default")
      (node (ref "J3") (pin "14") (pinfunction "14_14") (pintype "passive"))
      (node (ref "U1") (pin "P48") (pinfunction "IO47_P48") (pintype "bidirectional"))
    )
    (net (code "65") (name "LD0") (class "Default")
      (node (ref "J4") (pin "10") (pinfunction "10_10") (pintype "passive"))
      (node (ref "U1") (pin "P63") (pinfunction "LD0_P63") (pintype "bidirectional"))
    )
    (net (code "66") (name "LD1") (class "Default")
      (node (ref "J4") (pin "9") (pinfunction "9_9") (pintype "passive"))
      (node (ref "U1") (pin "P62") (pinfunction "LD1_P62") (pintype "bidirectional"))
    )
    (net (code "67") (name "LD2") (class "Default")
      (node (ref "J4") (pin "8") (pinfunction "8_8") (pintype "passive"))
      (node (ref "U1") (pin "P61") (pinfunction "LD2_P61") (pintype "bidirectional"))
    )
    (net (code "68") (name "LD3") (class "Default")
      (node (ref "J4") (pin "7") (pinfunction "7_7") (pintype "passive"))
      (node (ref "U1") (pin "P60") (pinfunction "LD3_P60") (pintype "bidirectional"))
    )
    (net (code "69") (name "LD4") (class "Default")
      (node (ref "J4") (pin "6") (pinfunction "6_6") (pintype "passive"))
      (node (ref "U1") (pin "P59") (pinfunction "LD4_P59") (pintype "bidirectional"))
    )
    (net (code "70") (name "LD5") (class "Default")
      (node (ref "J4") (pin "5") (pinfunction "5_5") (pintype "passive"))
      (node (ref "U1") (pin "P58") (pinfunction "LD5_P58") (pintype "bidirectional"))
    )
    (net (code "71") (name "LD6") (class "Default")
      (node (ref "J4") (pin "4") (pinfunction "4_4") (pintype "passive"))
      (node (ref "U1") (pin "P57") (pinfunction "LD6_P57") (pintype "bidirectional"))
    )
    (net (code "72") (name "LD7") (class "Default")
      (node (ref "J4") (pin "3") (pinfunction "3_3") (pintype "passive"))
      (node (ref "U1") (pin "P56") (pinfunction "LD7_P56") (pintype "bidirectional"))
    )
    (net (code "73") (name "Net-(LED1-Pad-)") (class "Default")
      (node (ref "LED1") (pin "-") (pinfunction "-_-") (pintype "passive"))
      (node (ref "R2") (pin "2") (pinfunction "2_2") (pintype "passive"))
    )
    (net (code "74") (name "Net-(LED2-Pad-)") (class "Default")
      (node (ref "LED2") (pin "-") (pinfunction "-_-") (pintype "passive"))
      (node (ref "R3") (pin "2") (pinfunction "2_2") (pintype "passive"))
    )
    (net (code "75") (name "Net-(Q1-B)") (class "Default")
      (node (ref "Q1") (pin "1") (pinfunction "B_1") (pintype "bidirectional"))
      (node (ref "R4") (pin "2") (pinfunction "2_2") (pintype "passive"))
    )
    (net (code "76") (name "Net-(Q2-B)") (class "Default")
      (node (ref "Q2") (pin "1") (pinfunction "B_1") (pintype "bidirectional"))
      (node (ref "R5") (pin "2") (pinfunction "2_2") (pintype "passive"))
    )
    (net (code "77") (name "Net-(U1-PAD)") (class "Default")
      (node (ref "U1") (pin "P73") (pinfunction "PAD_P73") (pintype "bidirectional"))
      (node (ref "ZTP1") (pin "TP") (pinfunction "TP_TP") (pintype "input"))
    )
    (net (code "78") (name "Net-(U1-PadP82)") (class "Default")
      (node (ref "U1") (pin "P82") (pinfunction "P82_P82") (pintype "bidirectional"))
      (node (ref "ZTP2") (pin "TP") (pinfunction "TP_TP") (pintype "input"))
    )
    (net (code "79") (name "Net-(U2-USBDM)") (class "Default")
      (node (ref "R6") (pin "1") (pinfunction "1_1") (pintype "passive"))
      (node (ref "U2") (pin "9") (pinfunction "USBDM_9") (pintype "bidirectional"))
    )
    (net (code "80") (name "Net-(U2-USBDP)") (class "Default")
      (node (ref "R7") (pin "1") (pinfunction "1_1") (pintype "passive"))
      (node (ref "U2") (pin "8") (pinfunction "USBDP_8") (pintype "bidirectional"))
    )
    (net (code "81") (name "Net-(USB1-CC1)") (class "Default")
      (node (ref "R9") (pin "1") (pinfunction "1_1") (pintype "passive"))
      (node (ref "USB1") (pin "A5") (pinfunction "CC1_A5") (pintype "bidirectional"))
    )
    (net (code "82") (name "Net-(USB1-CC2)") (class "Default")
      (node (ref "R8") (pin "1") (pinfunction "1_1") (pintype "passive"))
      (node (ref "USB1") (pin "B5") (pinfunction "CC2_B5") (pintype "bidirectional"))
    )
    (net (code "83") (name "RST") (class "Default")
      (node (ref "J4") (pin "2") (pinfunction "2_2") (pintype "passive"))
      (node (ref "J5") (pin "3") (pinfunction "3_3") (pintype "bidirectional"))
      (node (ref "J6") (pin "3") (pinfunction "3_3") (pintype "bidirectional"))
      (node (ref "K1") (pin "2") (pinfunction "2_2") (pintype "bidirectional"))
      (node (ref "K3") (pin "2") (pinfunction "2_2") (pintype "bidirectional"))
      (node (ref "Q1") (pin "3") (pinfunction "C_3") (pintype "bidirectional"))
      (node (ref "R1") (pin "1") (pinfunction "1_1") (pintype "passive"))
      (node (ref "U1") (pin "P55") (pinfunction "RST_P55") (pintype "bidirectional"))
    )
    (net (code "84") (name "RTS") (class "Default")
      (node (ref "Q1") (pin "2") (pinfunction "E_2") (pintype "bidirectional"))
      (node (ref "R5") (pin "1") (pinfunction "1_1") (pintype "passive"))
      (node (ref "U2") (pin "19") (pinfunction "RTS#_19") (pintype "bidirectional"))
    )
    (net (code "85") (name "V_USB") (class "Default")
      (node (ref "C13") (pin "2") (pinfunction "2_2") (pintype "passive"))
      (node (ref "C17") (pin "2") (pinfunction "2_2") (pintype "passive"))
      (node (ref "F1") (pin "1") (pinfunction "1_1") (pintype "bidirectional"))
      (node (ref "USB1") (pin "A4") (pinfunction "VBUS_A4") (pintype "power_in"))
      (node (ref "USB1") (pin "A9") (pinfunction "VBUS_A9") (pintype "power_in"))
      (node (ref "USB1") (pin "B4") (pinfunction "VBUS_B4") (pintype "power_in"))
      (node (ref "USB1") (pin "B9") (pinfunction "VBUS_B9") (pintype "power_in"))
    )
    (net (code "86") (name "WIO0") (class "Default")
      (node (ref "J1") (pin "2") (pinfunction "2_2") (pintype "passive"))
      (node (ref "U1") (pin "WI0") (pinfunction "WI0_WI0") (pintype "bidirectional"))
    )
    (net (code "87") (name "unconnected-(U1-PadP74)") (class "Default")
      (node (ref "U1") (pin "P74") (pinfunction "P74_P74") (pintype "bidirectional"))
    )
    (net (code "88") (name "unconnected-(U1-PadP75)") (class "Default")
      (node (ref "U1") (pin "P75") (pinfunction "P75_P75") (pintype "bidirectional"))
    )
    (net (code "89") (name "unconnected-(U1-PadP76)") (class "Default")
      (node (ref "U1") (pin "P76") (pinfunction "P76_P76") (pintype "bidirectional"))
    )
    (net (code "90") (name "unconnected-(U1-PadP77)") (class "Default")
      (node (ref "U1") (pin "P77") (pinfunction "P77_P77") (pintype "bidirectional"))
    )
    (net (code "91") (name "unconnected-(U1-PadP78)") (class "Default")
      (node (ref "U1") (pin "P78") (pinfunction "P78_P78") (pintype "bidirectional"))
    )
    (net (code "92") (name "unconnected-(U1-PadP79)") (class "Default")
      (node (ref "U1") (pin "P79") (pinfunction "P79_P79") (pintype "bidirectional"))
    )
    (net (code "93") (name "unconnected-(U1-PadP80)") (class "Default")
      (node (ref "U1") (pin "P80") (pinfunction "P80_P80") (pintype "bidirectional"))
    )
    (net (code "94") (name "unconnected-(U1-PadP81)") (class "Default")
      (node (ref "U1") (pin "P81") (pinfunction "P81_P81") (pintype "bidirectional"))
    )
    (net (code "95") (name "unconnected-(U2-CBUS0-Pad15)") (class "Default")
      (node (ref "U2") (pin "15") (pinfunction "CBUS0_15") (pintype "bidirectional"))
    )
    (net (code "96") (name "unconnected-(U2-CBUS1-Pad14)") (class "Default")
      (node (ref "U2") (pin "14") (pinfunction "CBUS1_14") (pintype "bidirectional"))
    )
    (net (code "97") (name "unconnected-(U2-CBUS2-Pad7)") (class "Default")
      (node (ref "U2") (pin "7") (pinfunction "CBUS2_7") (pintype "bidirectional"))
    )
    (net (code "98") (name "unconnected-(U2-CBUS3-Pad16)") (class "Default")
      (node (ref "U2") (pin "16") (pinfunction "CBUS3_16") (pintype "bidirectional"))
    )
    (net (code "99") (name "unconnected-(U2-CTS#-Pad6)") (class "Default")
      (node (ref "U2") (pin "6") (pinfunction "CTS#_6") (pintype "bidirectional"))
    )
    (net (code "100") (name "unconnected-(U2-DCD#-Pad5)") (class "Default")
      (node (ref "U2") (pin "5") (pinfunction "DCD#_5") (pintype "bidirectional"))
    )
    (net (code "101") (name "unconnected-(U2-DSR#-Pad4)") (class "Default")
      (node (ref "U2") (pin "4") (pinfunction "DSR#_4") (pintype "bidirectional"))
    )
    (net (code "102") (name "unconnected-(U2-RI#-Pad2)") (class "Default")
      (node (ref "U2") (pin "2") (pinfunction "RI#_2") (pintype "bidirectional"))
    )
    (net (code "103") (name "unconnected-(USB1-RX1+-PadB11)") (class "Default")
      (node (ref "USB1") (pin "B11") (pinfunction "RX1+_B11") (pintype "bidirectional"))
    )
    (net (code "104") (name "unconnected-(USB1-RX1--PadB10)") (class "Default")
      (node (ref "USB1") (pin "B10") (pinfunction "RX1-_B10") (pintype "bidirectional"))
    )
    (net (code "105") (name "unconnected-(USB1-RX2+-PadA11)") (class "Default")
      (node (ref "USB1") (pin "A11") (pinfunction "RX2+_A11") (pintype "bidirectional"))
    )
    (net (code "106") (name "unconnected-(USB1-RX2--PadA10)") (class "Default")
      (node (ref "USB1") (pin "A10") (pinfunction "RX2-_A10") (pintype "bidirectional"))
    )
    (net (code "107") (name "unconnected-(USB1-SBU1-PadA8)") (class "Default")
      (node (ref "USB1") (pin "A8") (pinfunction "SBU1_A8") (pintype "bidirectional"))
    )
    (net (code "108") (name "unconnected-(USB1-SBU2-PadB8)") (class "Default")
      (node (ref "USB1") (pin "B8") (pinfunction "SBU2_B8") (pintype "bidirectional"))
    )
    (net (code "109") (name "unconnected-(USB1-TX1+-PadA2)") (class "Default")
      (node (ref "USB1") (pin "A2") (pinfunction "TX1+_A2") (pintype "bidirectional"))
    )
    (net (code "110") (name "unconnected-(USB1-TX1--PadA3)") (class "Default")
      (node (ref "USB1") (pin "A3") (pinfunction "TX1-_A3") (pintype "bidirectional"))
    )
    (net (code "111") (name "unconnected-(USB1-TX2+-PadB2)") (class "Default")
      (node (ref "USB1") (pin "B2") (pinfunction "TX2+_B2") (pintype "bidirectional"))
    )
    (net (code "112") (name "unconnected-(USB1-TX2--PadB3)") (class "Default")
      (node (ref "USB1") (pin "B3") (pinfunction "TX2-_B3") (pintype "bidirectional"))
    )
  )
)
